# main.net
KiCad netlist of a schematic drawn in EAGLE
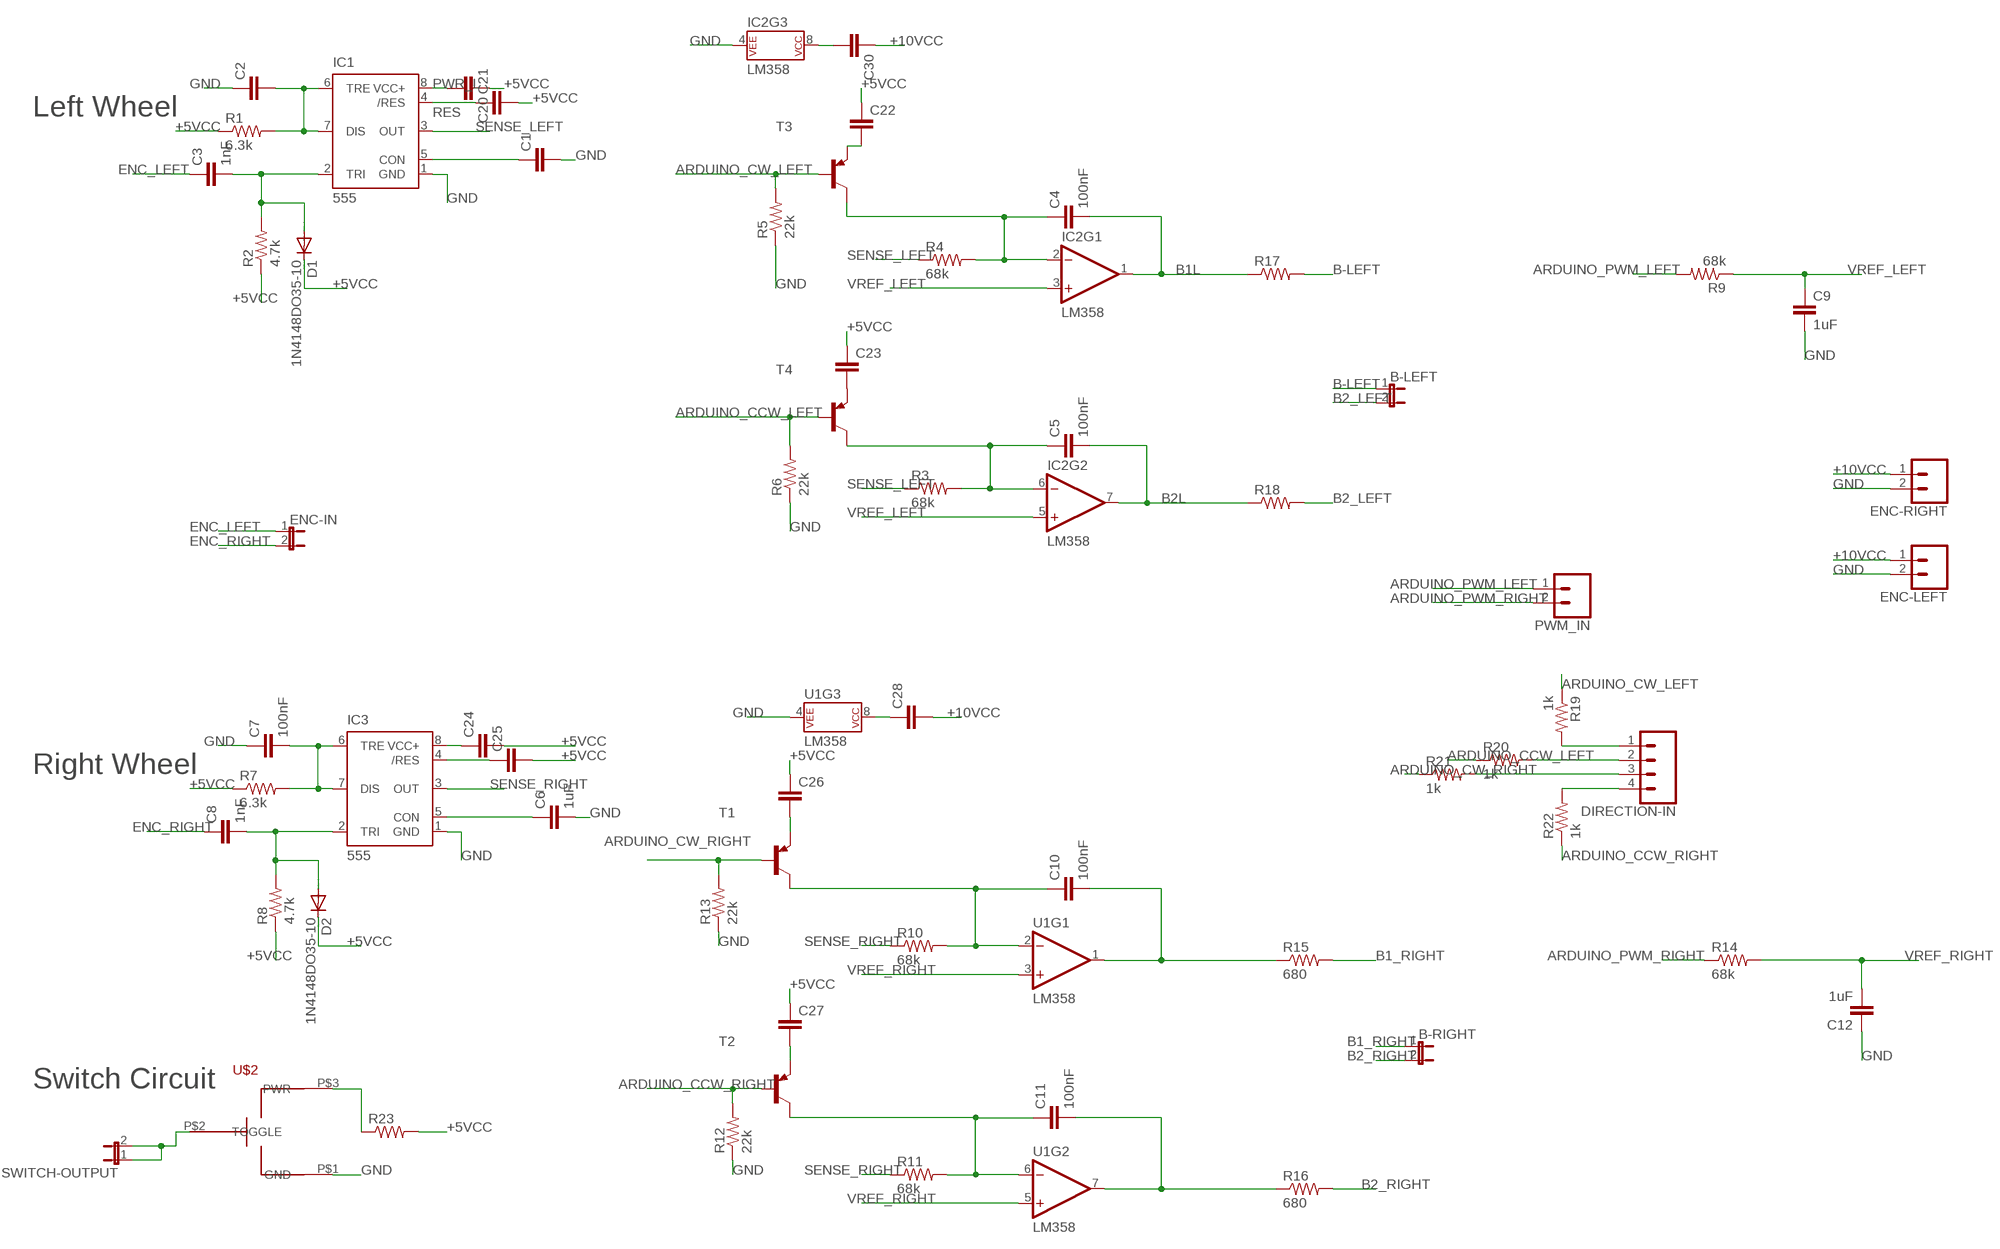
[diagram p0: schematic, sheet 1]

(export (version "E")
  (design (tool "Eeschema 10.0.6"))
  (components
    (comp (ref "B-LEFT")
      (value "JUMPER-2PTH")
      (footprint "eagle-import:1X02")
      (libsource (lib "eagle-import") (part "JUMPER-2PTH"))
    )
    (comp (ref "B-RIGHT")
      (value "JUMPER-2PTH")
      (footprint "eagle-import:1X02")
      (libsource (lib "eagle-import") (part "JUMPER-2PTH"))
    )
    (comp (ref "C1")
      (value "C5/2.5")
      (footprint "eagle-import:C5B2.5")
      (libsource (lib "eagle-import") (part "C5/2.5"))
    )
    (comp (ref "C2")
      (value "C5/2.5")
      (footprint "eagle-import:C5B2.5")
      (libsource (lib "eagle-import") (part "C5/2.5"))
    )
    (comp (ref "C3")
      (value "1nF")
      (footprint "eagle-import:C5B2.5")
      (libsource (lib "eagle-import") (part "C5/2.5"))
    )
    (comp (ref "C4")
      (value "100nF")
      (footprint "eagle-import:C5B2.5")
      (libsource (lib "eagle-import") (part "C5/2.5"))
    )
    (comp (ref "C5")
      (value "100nF")
      (footprint "eagle-import:C5B2.5")
      (libsource (lib "eagle-import") (part "C5/2.5"))
    )
    (comp (ref "C6")
      (value "1uF")
      (footprint "eagle-import:C5B2.5")
      (libsource (lib "eagle-import") (part "C5/2.5"))
    )
    (comp (ref "C7")
      (value "100nF")
      (footprint "eagle-import:C5B2.5")
      (libsource (lib "eagle-import") (part "C5/2.5"))
    )
    (comp (ref "C8")
      (value "1nF")
      (footprint "eagle-import:C5B2.5")
      (libsource (lib "eagle-import") (part "C5/2.5"))
    )
    (comp (ref "C9")
      (value "1uF")
      (footprint "eagle-import:C5B2.5")
      (libsource (lib "eagle-import") (part "C5/2.5"))
    )
    (comp (ref "C10")
      (value "100nF")
      (footprint "eagle-import:C5B2.5")
      (libsource (lib "eagle-import") (part "C5/2.5"))
    )
    (comp (ref "C11")
      (value "100nF")
      (footprint "eagle-import:C5B2.5")
      (libsource (lib "eagle-import") (part "C5/2.5"))
    )
    (comp (ref "C12")
      (value "1uF")
      (footprint "eagle-import:C5B2.5")
      (libsource (lib "eagle-import") (part "C5/2.5"))
    )
    (comp (ref "C20")
      (value "C5/2.5")
      (footprint "eagle-import:C5B2.5")
      (libsource (lib "eagle-import") (part "C5/2.5"))
    )
    (comp (ref "C21")
      (value "C5/2.5")
      (footprint "eagle-import:C5B2.5")
      (libsource (lib "eagle-import") (part "C5/2.5"))
    )
    (comp (ref "C22")
      (value "C5/2.5")
      (footprint "eagle-import:C5B2.5")
      (libsource (lib "eagle-import") (part "C5/2.5"))
    )
    (comp (ref "C23")
      (value "C5/2.5")
      (footprint "eagle-import:C5B2.5")
      (libsource (lib "eagle-import") (part "C5/2.5"))
    )
    (comp (ref "C24")
      (value "C5/2.5")
      (footprint "eagle-import:C5B2.5")
      (libsource (lib "eagle-import") (part "C5/2.5"))
    )
    (comp (ref "C25")
      (value "C5/2.5")
      (footprint "eagle-import:C5B2.5")
      (libsource (lib "eagle-import") (part "C5/2.5"))
    )
    (comp (ref "C26")
      (value "C5/2.5")
      (footprint "eagle-import:C5B2.5")
      (libsource (lib "eagle-import") (part "C5/2.5"))
    )
    (comp (ref "C27")
      (value "C5/2.5")
      (footprint "eagle-import:C5B2.5")
      (libsource (lib "eagle-import") (part "C5/2.5"))
    )
    (comp (ref "C28")
      (value "C5/2.5")
      (footprint "eagle-import:C5B2.5")
      (libsource (lib "eagle-import") (part "C5/2.5"))
    )
    (comp (ref "C30")
      (value "C5/2.5")
      (footprint "eagle-import:C5B2.5")
      (libsource (lib "eagle-import") (part "C5/2.5"))
    )
    (comp (ref "D1")
      (value "1N4148DO35-10")
      (footprint "eagle-import:DO35-10")
      (libsource (lib "eagle-import") (part "1N4148DO35-10"))
    )
    (comp (ref "D2")
      (value "1N4148DO35-10")
      (footprint "eagle-import:DO35-10")
      (libsource (lib "eagle-import") (part "1N4148DO35-10"))
    )
    (comp (ref "DIRECTION-IN")
      (value "CONN_04")
      (footprint "eagle-import:1X04")
      (libsource (lib "eagle-import") (part "CONN_04"))
    )
    (comp (ref "ENC-IN")
      (value "JUMPER-2PTH")
      (footprint "eagle-import:1X02")
      (libsource (lib "eagle-import") (part "JUMPER-2PTH"))
    )
    (comp (ref "ENC-LEFT")
      (value "CONN_02")
      (footprint "eagle-import:1X02")
      (libsource (lib "eagle-import") (part "CONN_02"))
    )
    (comp (ref "ENC-RIGHT")
      (value "CONN_02")
      (footprint "eagle-import:1X02")
      (libsource (lib "eagle-import") (part "CONN_02"))
    )
    (comp (ref "IC1")
      (value "555")
      (footprint "eagle-import:DIP08-KIT")
      (libsource (lib "eagle-import") (part "555KIT"))
    )
    (comp (ref "IC2")
      (value "LM358")
      (footprint "eagle-import:DIP08")
      (libsource (lib "eagle-import") (part "LM358"))
    )
    (comp (ref "IC3")
      (value "555")
      (footprint "eagle-import:DIP08-KIT")
      (libsource (lib "eagle-import") (part "555KIT"))
    )
    (comp (ref "PWM_IN")
      (value "CONN_02LOCK")
      (footprint "eagle-import:1X02_LOCK")
      (libsource (lib "eagle-import") (part "CONN_02LOCK"))
    )
    (comp (ref "R1")
      (value "6.3k")
      (footprint "eagle-import:0207_10")
      (libsource (lib "eagle-import") (part "R-US_0207/10"))
    )
    (comp (ref "R2")
      (value "4.7k")
      (footprint "eagle-import:0207_10")
      (libsource (lib "eagle-import") (part "R-US_0207/10"))
    )
    (comp (ref "R3")
      (value "68k")
      (footprint "eagle-import:0207_10")
      (libsource (lib "eagle-import") (part "R-US_0207/10"))
    )
    (comp (ref "R4")
      (value "68k")
      (footprint "eagle-import:0207_10")
      (libsource (lib "eagle-import") (part "R-US_0207/10"))
    )
    (comp (ref "R5")
      (value "22k")
      (footprint "eagle-import:0207_10")
      (libsource (lib "eagle-import") (part "R-US_0207/10"))
    )
    (comp (ref "R6")
      (value "22k")
      (footprint "eagle-import:0207_10")
      (libsource (lib "eagle-import") (part "R-US_0207/10"))
    )
    (comp (ref "R7")
      (value "6.3k")
      (footprint "eagle-import:0207_10")
      (libsource (lib "eagle-import") (part "R-US_0207/10"))
    )
    (comp (ref "R8")
      (value "4.7k")
      (footprint "eagle-import:0207_10")
      (libsource (lib "eagle-import") (part "R-US_0207/10"))
    )
    (comp (ref "R9")
      (value "68k")
      (footprint "eagle-import:0207_10")
      (libsource (lib "eagle-import") (part "R-US_0207/10"))
    )
    (comp (ref "R10")
      (value "68k")
      (footprint "eagle-import:0207_10")
      (libsource (lib "eagle-import") (part "R-US_0207/10"))
    )
    (comp (ref "R11")
      (value "68k")
      (footprint "eagle-import:0207_10")
      (libsource (lib "eagle-import") (part "R-US_0207/10"))
    )
    (comp (ref "R12")
      (value "22k")
      (footprint "eagle-import:0207_10")
      (libsource (lib "eagle-import") (part "R-US_0207/10"))
    )
    (comp (ref "R13")
      (value "22k")
      (footprint "eagle-import:0207_10")
      (libsource (lib "eagle-import") (part "R-US_0207/10"))
    )
    (comp (ref "R14")
      (value "68k")
      (footprint "eagle-import:0207_10")
      (libsource (lib "eagle-import") (part "R-US_0207/10"))
    )
    (comp (ref "R15")
      (value "680")
      (footprint "eagle-import:0207_10")
      (libsource (lib "eagle-import") (part "R-US_0207/10"))
    )
    (comp (ref "R16")
      (value "680")
      (footprint "eagle-import:0207_10")
      (libsource (lib "eagle-import") (part "R-US_0207/10"))
    )
    (comp (ref "R17")
      (value "R-US_0207/10")
      (footprint "eagle-import:0207_10")
      (libsource (lib "eagle-import") (part "R-US_0207/10"))
    )
    (comp (ref "R18")
      (value "R-US_0207/10")
      (footprint "eagle-import:0207_10")
      (libsource (lib "eagle-import") (part "R-US_0207/10"))
    )
    (comp (ref "R19")
      (value "1k")
      (footprint "eagle-import:0207_10")
      (libsource (lib "eagle-import") (part "R-US_0207/10"))
    )
    (comp (ref "R20")
      (value "1k")
      (footprint "eagle-import:0207_10")
      (libsource (lib "eagle-import") (part "R-US_0207/10"))
    )
    (comp (ref "R21")
      (value "1k")
      (footprint "eagle-import:0207_10")
      (libsource (lib "eagle-import") (part "R-US_0207/10"))
    )
    (comp (ref "R22")
      (value "1k")
      (footprint "eagle-import:0207_10")
      (libsource (lib "eagle-import") (part "R-US_0207/10"))
    )
    (comp (ref "R23")
      (value "R-US_0207/10")
      (footprint "eagle-import:0207_10")
      (libsource (lib "eagle-import") (part "R-US_0207/10"))
    )
    (comp (ref "SWITCH-OUTPUT")
      (value "JUMPER-2PTH")
      (footprint "eagle-import:1X02")
      (libsource (lib "eagle-import") (part "JUMPER-2PTH"))
    )
    (comp (ref "T1")
      (value "2N4126-PNP-TO92-CBE")
      (footprint "eagle-import:TO92-CBE")
      (libsource (lib "eagle-import") (part "-PNP-TO92-CBE2N4126"))
    )
    (comp (ref "T2")
      (value "2N4126-PNP-TO92-CBE")
      (footprint "eagle-import:TO92-CBE")
      (libsource (lib "eagle-import") (part "-PNP-TO92-CBE2N4126"))
    )
    (comp (ref "T3")
      (value "2N4126-PNP-TO92-CBE")
      (footprint "eagle-import:TO92-CBE")
      (libsource (lib "eagle-import") (part "-PNP-TO92-CBE2N4126"))
    )
    (comp (ref "T4")
      (value "2N4126-PNP-TO92-CBE")
      (footprint "eagle-import:TO92-CBE")
      (libsource (lib "eagle-import") (part "-PNP-TO92-CBE2N4126"))
    )
    (comp (ref "U$2")
      (value "SWITCH")
      (footprint "eagle-import:SWITCH")
      (libsource (lib "eagle-import") (part "SWITCH"))
    )
    (comp (ref "U1")
      (value "LM358")
      (footprint "eagle-import:DIP08")
      (libsource (lib "eagle-import") (part "LM358"))
    )
  )
  (nets
    (net (code "1") (name "/+5VCC") (class "Default")
      (node (ref "C20") (pin "1") (pinfunction "1_1") (pintype "passive"))
      (node (ref "C21") (pin "2") (pinfunction "2_2") (pintype "passive"))
      (node (ref "C22") (pin "1") (pinfunction "1_1") (pintype "passive"))
      (node (ref "C23") (pin "1") (pinfunction "1_1") (pintype "passive"))
      (node (ref "C24") (pin "2") (pinfunction "2_2") (pintype "passive"))
      (node (ref "C25") (pin "2") (pinfunction "2_2") (pintype "passive"))
      (node (ref "C26") (pin "1") (pinfunction "1_1") (pintype "passive"))
      (node (ref "C27") (pin "1") (pinfunction "1_1") (pintype "passive"))
      (node (ref "D1") (pin "C") (pinfunction "C_C") (pintype "passive"))
      (node (ref "D2") (pin "C") (pinfunction "C_C") (pintype "passive"))
      (node (ref "R1") (pin "1") (pinfunction "1_1") (pintype "passive"))
      (node (ref "R2") (pin "1") (pinfunction "1_1") (pintype "passive"))
      (node (ref "R23") (pin "2") (pinfunction "2_2") (pintype "passive"))
      (node (ref "R7") (pin "1") (pinfunction "1_1") (pintype "passive"))
      (node (ref "R8") (pin "1") (pinfunction "1_1") (pintype "passive"))
    )
    (net (code "2") (name "/+10VCC") (class "Default")
      (node (ref "C28") (pin "2") (pinfunction "2_2") (pintype "passive"))
      (node (ref "C30") (pin "1") (pinfunction "1_1") (pintype "passive"))
      (node (ref "ENC-LEFT") (pin "1") (pinfunction "1_1") (pintype "passive"))
      (node (ref "ENC-RIGHT") (pin "1") (pinfunction "1_1") (pintype "passive"))
    )
    (net (code "3") (name "/ARDUINO_CCW_LEFT") (class "Default")
      (node (ref "R20") (pin "1") (pinfunction "1_1") (pintype "passive"))
      (node (ref "R6") (pin "2") (pinfunction "2_2") (pintype "passive"))
      (node (ref "T4") (pin "B") (pinfunction "B_B") (pintype "passive"))
    )
    (net (code "4") (name "/ARDUINO_CCW_RIGHT") (class "Default")
      (node (ref "R12") (pin "2") (pinfunction "2_2") (pintype "passive"))
      (node (ref "R22") (pin "1") (pinfunction "1_1") (pintype "passive"))
      (node (ref "T2") (pin "B") (pinfunction "B_B") (pintype "passive"))
    )
    (net (code "5") (name "/ARDUINO_CW_LEFT") (class "Default")
      (node (ref "R19") (pin "1") (pinfunction "1_1") (pintype "passive"))
      (node (ref "R5") (pin "2") (pinfunction "2_2") (pintype "passive"))
      (node (ref "T3") (pin "B") (pinfunction "B_B") (pintype "passive"))
    )
    (net (code "6") (name "/ARDUINO_CW_RIGHT") (class "Default")
      (node (ref "R13") (pin "2") (pinfunction "2_2") (pintype "passive"))
      (node (ref "R21") (pin "1") (pinfunction "1_1") (pintype "passive"))
      (node (ref "T1") (pin "B") (pinfunction "B_B") (pintype "passive"))
    )
    (net (code "7") (name "/ARDUINO_PWM_LEFT") (class "Default")
      (node (ref "PWM_IN") (pin "1") (pinfunction "1_1") (pintype "passive"))
      (node (ref "R9") (pin "2") (pinfunction "2_2") (pintype "passive"))
    )
    (net (code "8") (name "/ARDUINO_PWM_RIGHT") (class "Default")
      (node (ref "PWM_IN") (pin "2") (pinfunction "2_2") (pintype "passive"))
      (node (ref "R14") (pin "1") (pinfunction "1_1") (pintype "passive"))
    )
    (net (code "9") (name "/B-LEFT") (class "Default")
      (node (ref "B-LEFT") (pin "1") (pinfunction "1_1") (pintype "passive"))
      (node (ref "R17") (pin "2") (pinfunction "2_2") (pintype "passive"))
    )
    (net (code "10") (name "/B1L") (class "Default")
      (node (ref "C4") (pin "2") (pinfunction "2_2") (pintype "passive"))
      (node (ref "IC2") (pin "1") (pinfunction "OUT_1") (pintype "output"))
      (node (ref "R17") (pin "1") (pinfunction "1_1") (pintype "passive"))
    )
    (net (code "11") (name "/B1_RIGHT") (class "Default")
      (node (ref "B-RIGHT") (pin "1") (pinfunction "1_1") (pintype "passive"))
      (node (ref "R15") (pin "2") (pinfunction "2_2") (pintype "passive"))
    )
    (net (code "12") (name "/B2L") (class "Default")
      (node (ref "C5") (pin "2") (pinfunction "2_2") (pintype "passive"))
      (node (ref "IC2") (pin "7") (pinfunction "OUT_7") (pintype "output"))
      (node (ref "R18") (pin "1") (pinfunction "1_1") (pintype "passive"))
    )
    (net (code "13") (name "/B2_LEFT") (class "Default")
      (node (ref "B-LEFT") (pin "2") (pinfunction "2_2") (pintype "passive"))
      (node (ref "R18") (pin "2") (pinfunction "2_2") (pintype "passive"))
    )
    (net (code "14") (name "/B2_RIGHT") (class "Default")
      (node (ref "B-RIGHT") (pin "2") (pinfunction "2_2") (pintype "passive"))
      (node (ref "R16") (pin "2") (pinfunction "2_2") (pintype "passive"))
    )
    (net (code "15") (name "/ENC_LEFT") (class "Default")
      (node (ref "C3") (pin "1") (pinfunction "1_1") (pintype "passive"))
      (node (ref "ENC-IN") (pin "1") (pinfunction "1_1") (pintype "passive"))
    )
    (net (code "16") (name "/ENC_RIGHT") (class "Default")
      (node (ref "C8") (pin "1") (pinfunction "1_1") (pintype "passive"))
      (node (ref "ENC-IN") (pin "2") (pinfunction "2_2") (pintype "passive"))
    )
    (net (code "17") (name "/GND") (class "Default")
      (node (ref "C1") (pin "2") (pinfunction "2_2") (pintype "passive"))
      (node (ref "C12") (pin "1") (pinfunction "1_1") (pintype "passive"))
      (node (ref "C2") (pin "1") (pinfunction "1_1") (pintype "passive"))
      (node (ref "C6") (pin "2") (pinfunction "2_2") (pintype "passive"))
      (node (ref "C7") (pin "1") (pinfunction "1_1") (pintype "passive"))
      (node (ref "C9") (pin "2") (pinfunction "2_2") (pintype "passive"))
      (node (ref "ENC-LEFT") (pin "2") (pinfunction "2_2") (pintype "passive"))
      (node (ref "ENC-RIGHT") (pin "2") (pinfunction "2_2") (pintype "passive"))
      (node (ref "IC1") (pin "1") (pinfunction "GND_1") (pintype "power_in"))
      (node (ref "IC2") (pin "4") (pinfunction "P$V-_4") (pintype "bidirectional"))
      (node (ref "IC3") (pin "1") (pinfunction "GND_1") (pintype "power_in"))
      (node (ref "R12") (pin "1") (pinfunction "1_1") (pintype "passive"))
      (node (ref "R13") (pin "1") (pinfunction "1_1") (pintype "passive"))
      (node (ref "R5") (pin "1") (pinfunction "1_1") (pintype "passive"))
      (node (ref "R6") (pin "1") (pinfunction "1_1") (pintype "passive"))
      (node (ref "U$2") (pin "P$1") (pinfunction "GND_P$1") (pintype "bidirectional"))
      (node (ref "U1") (pin "4") (pinfunction "P$V-_4") (pintype "bidirectional"))
    )
    (net (code "18") (name "/PWR_L") (class "Default")
      (node (ref "C20") (pin "2") (pinfunction "2_2") (pintype "passive"))
      (node (ref "IC1") (pin "8") (pinfunction "VCC+_8") (pintype "power_in"))
    )
    (net (code "19") (name "/RES") (class "Default")
      (node (ref "C21") (pin "1") (pinfunction "1_1") (pintype "passive"))
      (node (ref "IC1") (pin "4") (pinfunction "/RES_4") (pintype "input"))
    )
    (net (code "20") (name "/SENSE_LEFT") (class "Default")
      (node (ref "IC1") (pin "3") (pinfunction "OUT_3") (pintype "output"))
      (node (ref "R3") (pin "1") (pinfunction "1_1") (pintype "passive"))
      (node (ref "R4") (pin "1") (pinfunction "1_1") (pintype "passive"))
    )
    (net (code "21") (name "/SENSE_RIGHT") (class "Default")
      (node (ref "IC3") (pin "3") (pinfunction "OUT_3") (pintype "output"))
      (node (ref "R10") (pin "1") (pinfunction "1_1") (pintype "passive"))
      (node (ref "R11") (pin "1") (pinfunction "1_1") (pintype "passive"))
    )
    (net (code "22") (name "/VREF_LEFT") (class "Default")
      (node (ref "C9") (pin "1") (pinfunction "1_1") (pintype "passive"))
      (node (ref "IC2") (pin "3") (pinfunction "+IN_3") (pintype "input"))
      (node (ref "IC2") (pin "5") (pinfunction "+IN_5") (pintype "input"))
      (node (ref "R9") (pin "1") (pinfunction "1_1") (pintype "passive"))
    )
    (net (code "23") (name "/VREF_RIGHT") (class "Default")
      (node (ref "C12") (pin "2") (pinfunction "2_2") (pintype "passive"))
      (node (ref "R14") (pin "2") (pinfunction "2_2") (pintype "passive"))
      (node (ref "U1") (pin "3") (pinfunction "+IN_3") (pintype "input"))
      (node (ref "U1") (pin "5") (pinfunction "+IN_5") (pintype "input"))
    )
    (net (code "24") (name "Net-(C22-Pad2)") (class "Default")
      (node (ref "C22") (pin "2") (pinfunction "2_2") (pintype "passive"))
      (node (ref "T3") (pin "E") (pinfunction "E_E") (pintype "passive"))
    )
    (net (code "25") (name "Net-(C23-Pad2)") (class "Default")
      (node (ref "C23") (pin "2") (pinfunction "2_2") (pintype "passive"))
      (node (ref "T4") (pin "E") (pinfunction "E_E") (pintype "passive"))
    )
    (net (code "26") (name "Net-(C26-Pad2)") (class "Default")
      (node (ref "C26") (pin "2") (pinfunction "2_2") (pintype "passive"))
      (node (ref "T1") (pin "E") (pinfunction "E_E") (pintype "passive"))
    )
    (net (code "27") (name "Net-(C27-Pad2)") (class "Default")
      (node (ref "C27") (pin "2") (pinfunction "2_2") (pintype "passive"))
      (node (ref "T2") (pin "E") (pinfunction "E_E") (pintype "passive"))
    )
    (net (code "28") (name "Net-(DIRECTION-IN-Pad1)") (class "Default")
      (node (ref "DIRECTION-IN") (pin "1") (pinfunction "1_1") (pintype "passive"))
      (node (ref "R19") (pin "2") (pinfunction "2_2") (pintype "passive"))
    )
    (net (code "29") (name "Net-(DIRECTION-IN-Pad2)") (class "Default")
      (node (ref "DIRECTION-IN") (pin "2") (pinfunction "2_2") (pintype "passive"))
      (node (ref "R20") (pin "2") (pinfunction "2_2") (pintype "passive"))
    )
    (net (code "30") (name "Net-(DIRECTION-IN-Pad3)") (class "Default")
      (node (ref "DIRECTION-IN") (pin "3") (pinfunction "3_3") (pintype "passive"))
      (node (ref "R21") (pin "2") (pinfunction "2_2") (pintype "passive"))
    )
    (net (code "31") (name "Net-(DIRECTION-IN-Pad4)") (class "Default")
      (node (ref "DIRECTION-IN") (pin "4") (pinfunction "4_4") (pintype "passive"))
      (node (ref "R22") (pin "2") (pinfunction "2_2") (pintype "passive"))
    )
    (net (code "32") (name "Net-(IC1-CON)") (class "Default")
      (node (ref "C1") (pin "1") (pinfunction "1_1") (pintype "passive"))
      (node (ref "IC1") (pin "5") (pinfunction "CON_5") (pintype "input"))
    )
    (net (code "33") (name "Net-(IC1-DIS)") (class "Default")
      (node (ref "C2") (pin "2") (pinfunction "2_2") (pintype "passive"))
      (node (ref "IC1") (pin "6") (pinfunction "TRE_6") (pintype "input"))
      (node (ref "IC1") (pin "7") (pinfunction "DIS_7") (pintype "input"))
      (node (ref "R1") (pin "2") (pinfunction "2_2") (pintype "passive"))
    )
    (net (code "34") (name "Net-(IC1-TRI)") (class "Default")
      (node (ref "C3") (pin "2") (pinfunction "2_2") (pintype "passive"))
      (node (ref "D1") (pin "A") (pinfunction "A_A") (pintype "passive"))
      (node (ref "IC1") (pin "2") (pinfunction "TRI_2") (pintype "input"))
      (node (ref "R2") (pin "2") (pinfunction "2_2") (pintype "passive"))
    )
    (net (code "35") (name "Net-(IC2A--IN)") (class "Default")
      (node (ref "C4") (pin "1") (pinfunction "1_1") (pintype "passive"))
      (node (ref "IC2") (pin "2") (pinfunction "-IN_2") (pintype "input"))
      (node (ref "R4") (pin "2") (pinfunction "2_2") (pintype "passive"))
      (node (ref "T3") (pin "C") (pinfunction "C_C") (pintype "passive"))
    )
    (net (code "36") (name "Net-(IC2B--IN)") (class "Default")
      (node (ref "C5") (pin "1") (pinfunction "1_1") (pintype "passive"))
      (node (ref "IC2") (pin "6") (pinfunction "-IN_6") (pintype "input"))
      (node (ref "R3") (pin "2") (pinfunction "2_2") (pintype "passive"))
      (node (ref "T4") (pin "C") (pinfunction "C_C") (pintype "passive"))
    )
    (net (code "37") (name "Net-(IC2C-P$V+)") (class "Default")
      (node (ref "C30") (pin "2") (pinfunction "2_2") (pintype "passive"))
      (node (ref "IC2") (pin "8") (pinfunction "P$V+_8") (pintype "bidirectional"))
    )
    (net (code "38") (name "Net-(IC3-CON)") (class "Default")
      (node (ref "C6") (pin "1") (pinfunction "1_1") (pintype "passive"))
      (node (ref "IC3") (pin "5") (pinfunction "CON_5") (pintype "input"))
    )
    (net (code "39") (name "Net-(IC3-DIS)") (class "Default")
      (node (ref "C7") (pin "2") (pinfunction "2_2") (pintype "passive"))
      (node (ref "IC3") (pin "6") (pinfunction "TRE_6") (pintype "input"))
      (node (ref "IC3") (pin "7") (pinfunction "DIS_7") (pintype "input"))
      (node (ref "R7") (pin "2") (pinfunction "2_2") (pintype "passive"))
    )
    (net (code "40") (name "Net-(IC3-TRI)") (class "Default")
      (node (ref "C8") (pin "2") (pinfunction "2_2") (pintype "passive"))
      (node (ref "D2") (pin "A") (pinfunction "A_A") (pintype "passive"))
      (node (ref "IC3") (pin "2") (pinfunction "TRI_2") (pintype "input"))
      (node (ref "R8") (pin "2") (pinfunction "2_2") (pintype "passive"))
    )
    (net (code "41") (name "Net-(IC3-VCC+)") (class "Default")
      (node (ref "C24") (pin "1") (pinfunction "1_1") (pintype "passive"))
      (node (ref "IC3") (pin "8") (pinfunction "VCC+_8") (pintype "power_in"))
    )
    (net (code "42") (name "Net-(IC3-{slash}RES)") (class "Default")
      (node (ref "C25") (pin "1") (pinfunction "1_1") (pintype "passive"))
      (node (ref "IC3") (pin "4") (pinfunction "/RES_4") (pintype "input"))
    )
    (net (code "43") (name "Net-(U$2-PWR)") (class "Default")
      (node (ref "R23") (pin "1") (pinfunction "1_1") (pintype "passive"))
      (node (ref "U$2") (pin "P$3") (pinfunction "PWR_P$3") (pintype "bidirectional"))
    )
    (net (code "44") (name "Net-(U$2-TOGGLE)") (class "Default")
      (node (ref "SWITCH-OUTPUT") (pin "1") (pinfunction "1_1") (pintype "passive"))
      (node (ref "SWITCH-OUTPUT") (pin "2") (pinfunction "2_2") (pintype "passive"))
      (node (ref "U$2") (pin "P$2") (pinfunction "TOGGLE_P$2") (pintype "bidirectional"))
    )
    (net (code "45") (name "Net-(U1A--IN)") (class "Default")
      (node (ref "C10") (pin "1") (pinfunction "1_1") (pintype "passive"))
      (node (ref "R10") (pin "2") (pinfunction "2_2") (pintype "passive"))
      (node (ref "T1") (pin "C") (pinfunction "C_C") (pintype "passive"))
      (node (ref "U1") (pin "2") (pinfunction "-IN_2") (pintype "input"))
    )
    (net (code "46") (name "Net-(U1A-OUT)") (class "Default")
      (node (ref "C10") (pin "2") (pinfunction "2_2") (pintype "passive"))
      (node (ref "R15") (pin "1") (pinfunction "1_1") (pintype "passive"))
      (node (ref "U1") (pin "1") (pinfunction "OUT_1") (pintype "output"))
    )
    (net (code "47") (name "Net-(U1B--IN)") (class "Default")
      (node (ref "C11") (pin "1") (pinfunction "1_1") (pintype "passive"))
      (node (ref "R11") (pin "2") (pinfunction "2_2") (pintype "passive"))
      (node (ref "T2") (pin "C") (pinfunction "C_C") (pintype "passive"))
      (node (ref "U1") (pin "6") (pinfunction "-IN_6") (pintype "input"))
    )
    (net (code "48") (name "Net-(U1B-OUT)") (class "Default")
      (node (ref "C11") (pin "2") (pinfunction "2_2") (pintype "passive"))
      (node (ref "R16") (pin "1") (pinfunction "1_1") (pintype "passive"))
      (node (ref "U1") (pin "7") (pinfunction "OUT_7") (pintype "output"))
    )
    (net (code "49") (name "Net-(U1C-P$V+)") (class "Default")
      (node (ref "C28") (pin "1") (pinfunction "1_1") (pintype "passive"))
      (node (ref "U1") (pin "8") (pinfunction "P$V+_8") (pintype "bidirectional"))
    )
  )
)
